# Microcontroller.net
KiCad netlist of a schematic drawn in Altium Designer
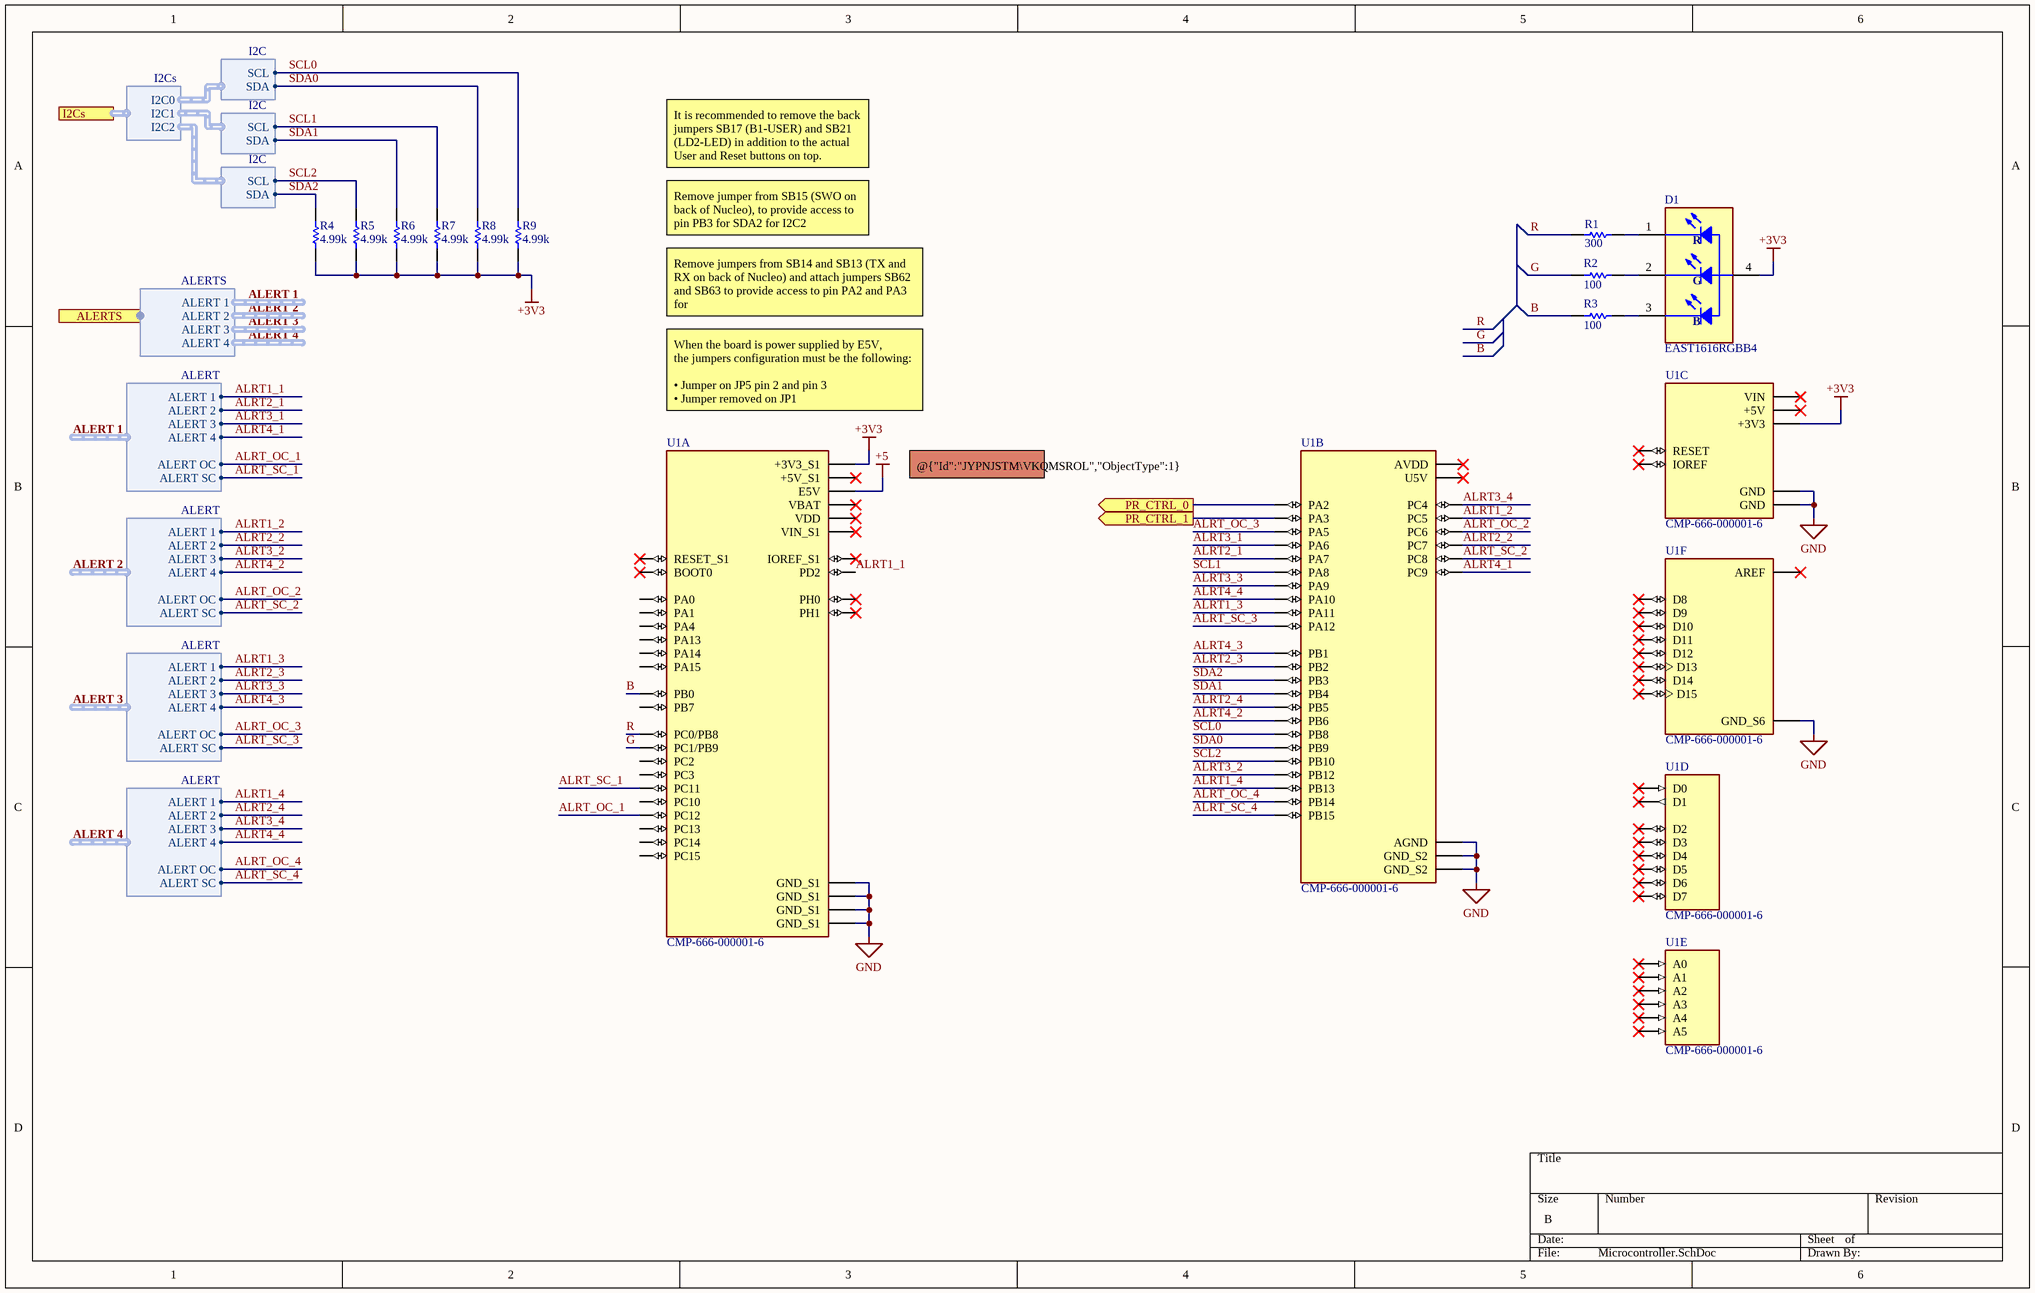
[diagram p0: Microcontroller.SchDoc]

(export (version "E")
  (design (tool "Eeschema 10.0.6"))
  (components
    (comp (ref "D1")
      (value "EAST1616RGBB4")
      (footprint "FP-EAST1616RGBB4-MFG")
      (description "Triple Color LED")
      (libsource (lib "IIT Motorsports") (part "36fc5605c777916eb4f03788a33f3b3"))
    )
    (comp (ref "R1")
      (value "300")
      (footprint "RES 0805_2012")
      (fields
        (field (name "TOLERANCE") "1%")
        (field (name "POWER") "125mW")
        (field (name "Comment") "ERJ-6ENF3000V")
      )
      (libsource (lib "IIT Motorsports") (part "RES"))
    )
    (comp (ref "R2")
      (value "100")
      (footprint "RES 0805_2012")
      (fields
        (field (name "TOLERANCE") "1%")
        (field (name "MP") "CRG0805F100R")
        (field (name "MF") "{'manufacturer': u'TE Connectivity'}")
      )
      (libsource (lib "IIT Motorsports") (part "CMP-009-00299-2"))
    )
    (comp (ref "R3")
      (value "100")
      (footprint "RES 0805_2012")
      (fields
        (field (name "TOLERANCE") "1%")
        (field (name "MP") "CRG0805F100R")
        (field (name "MF") "{'manufacturer': u'TE Connectivity'}")
      )
      (libsource (lib "IIT Motorsports") (part "CMP-009-00299-2"))
    )
    (comp (ref "R4")
      (value "4.99k")
      (footprint "RES 0805_2012")
      (fields
        (field (name "TOLERANCE") "1%")
        (field (name "POWER") "125mW")
        (field (name "Comment") "ERJ-6ENF4991V")
      )
      (libsource (lib "IIT Motorsports") (part "RES"))
    )
    (comp (ref "R5")
      (value "4.99k")
      (footprint "RES 0805_2012")
      (fields
        (field (name "TOLERANCE") "1%")
        (field (name "POWER") "125mW")
        (field (name "Comment") "ERJ-6ENF4991V")
      )
      (libsource (lib "IIT Motorsports") (part "RES"))
    )
    (comp (ref "R6")
      (value "4.99k")
      (footprint "RES 0805_2012")
      (fields
        (field (name "POWER") "125mW")
        (field (name "TOLERANCE") "1%")
        (field (name "Comment") "ERJ-6ENF4991V")
      )
      (libsource (lib "IIT Motorsports") (part "RES"))
    )
    (comp (ref "R7")
      (value "4.99k")
      (footprint "RES 0805_2012")
      (fields
        (field (name "POWER") "125mW")
        (field (name "TOLERANCE") "1%")
        (field (name "Comment") "ERJ-6ENF4991V")
      )
      (libsource (lib "IIT Motorsports") (part "RES"))
    )
    (comp (ref "R8")
      (value "4.99k")
      (footprint "RES 0805_2012")
      (fields
        (field (name "POWER") "125mW")
        (field (name "TOLERANCE") "1%")
        (field (name "Comment") "ERJ-6ENF4991V")
      )
      (libsource (lib "IIT Motorsports") (part "RES"))
    )
    (comp (ref "R9")
      (value "4.99k")
      (footprint "RES 0805_2012")
      (fields
        (field (name "POWER") "125mW")
        (field (name "TOLERANCE") "1%")
        (field (name "Comment") "ERJ-6ENF4991V")
      )
      (libsource (lib "IIT Motorsports") (part "RES"))
    )
    (comp (ref "U1")
      (value "CMP-666-000001-6")
      (footprint "ST_NUCLEO-F401RE")
      (description "STM32F401RE Embedded Nucleo STM32F4 MCU 32-Bit ARM Cortex-M3 Evaluation Board")
      (fields (field (name "MP") "NUCLEO-F401RE") (field (name "MF") "STMicroelectronics"))
      (libsource (lib "IIT Motorsports") (part "CMP-666-000001-6"))
    )
  )
  (nets
    (net (code "7") (name "+3V3") (class "Default")
      (node (ref "D1") (pin "4") (pinfunction "COMMON_ANODE_4") (pintype "passive"))
      (node (ref "R4") (pin "1") (pinfunction "1_1") (pintype "passive"))
      (node (ref "R5") (pin "1") (pinfunction "1_1") (pintype "passive"))
      (node (ref "R6") (pin "1") (pinfunction "1_1") (pintype "passive"))
      (node (ref "R7") (pin "1") (pinfunction "1_1") (pintype "passive"))
      (node (ref "R8") (pin "1") (pinfunction "1_1") (pintype "passive"))
      (node (ref "R9") (pin "1") (pinfunction "1_1") (pintype "passive"))
      (node (ref "U1") (pin "CN6_4") (pinfunction "+3V3_CN6_4") (pintype "power_in"))
      (node (ref "U1") (pin "CN7_16") (pinfunction "+3V3_S1_CN7_16") (pintype "power_in"))
    )
    (net (code "8") (name "+5") (class "Default")
      (node (ref "U1") (pin "CN7_6") (pinfunction "E5V_CN7_6") (pintype "power_in"))
    )
    (net (code "10") (name "/ALRT1_1") (class "Default")
      (node (ref "U1") (pin "CN7_4") (pinfunction "PD2_CN7_4") (pintype "bidirectional"))
    )
    (net (code "11") (name "/ALRT1_2") (class "Default")
      (node (ref "U1") (pin "CN10_6") (pinfunction "PC5_CN10_6") (pintype "bidirectional"))
    )
    (net (code "12") (name "/ALRT1_3") (class "Default")
      (node (ref "U1") (pin "CN10_14") (pinfunction "PA11_CN10_14") (pintype "bidirectional"))
    )
    (net (code "13") (name "/ALRT1_4") (class "Default")
      (node (ref "U1") (pin "CN10_30") (pinfunction "PB13_CN10_30") (pintype "bidirectional"))
    )
    (net (code "14") (name "/ALRT2_1") (class "Default")
      (node (ref "U1") (pin "CN10_15") (pinfunction "PA7_CN10_15") (pintype "bidirectional"))
    )
    (net (code "15") (name "/ALRT2_2") (class "Default")
      (node (ref "U1") (pin "CN10_19") (pinfunction "PC7_CN10_19") (pintype "bidirectional"))
    )
    (net (code "16") (name "/ALRT2_3") (class "Default")
      (node (ref "U1") (pin "CN10_22") (pinfunction "PB2_CN10_22") (pintype "bidirectional"))
    )
    (net (code "17") (name "/ALRT2_4") (class "Default")
      (node (ref "U1") (pin "CN10_29") (pinfunction "PB5_CN10_29") (pintype "bidirectional"))
    )
    (net (code "18") (name "/ALRT3_1") (class "Default")
      (node (ref "U1") (pin "CN10_13") (pinfunction "PA6_CN10_13") (pintype "bidirectional"))
    )
    (net (code "19") (name "/ALRT3_2") (class "Default")
      (node (ref "U1") (pin "CN10_16") (pinfunction "PB12_CN10_16") (pintype "bidirectional"))
    )
    (net (code "20") (name "/ALRT3_3") (class "Default")
      (node (ref "U1") (pin "CN10_21") (pinfunction "PA9_CN10_21") (pintype "bidirectional"))
    )
    (net (code "21") (name "/ALRT3_4") (class "Default")
      (node (ref "U1") (pin "CN10_34") (pinfunction "PC4_CN10_34") (pintype "bidirectional"))
    )
    (net (code "22") (name "/ALRT4_1") (class "Default")
      (node (ref "U1") (pin "CN10_1") (pinfunction "PC9_CN10_1") (pintype "bidirectional"))
    )
    (net (code "23") (name "/ALRT4_2") (class "Default")
      (node (ref "U1") (pin "CN10_17") (pinfunction "PB6_CN10_17") (pintype "bidirectional"))
    )
    (net (code "24") (name "/ALRT4_3") (class "Default")
      (node (ref "U1") (pin "CN10_24") (pinfunction "PB1_CN10_24") (pintype "bidirectional"))
    )
    (net (code "25") (name "/ALRT4_4") (class "Default")
      (node (ref "U1") (pin "CN10_33") (pinfunction "PA10_CN10_33") (pintype "bidirectional"))
    )
    (net (code "26") (name "/ALRT_OC_1") (class "Default")
      (node (ref "U1") (pin "CN7_3") (pinfunction "PC12_CN7_3") (pintype "bidirectional"))
    )
    (net (code "27") (name "/ALRT_OC_2") (class "Default")
      (node (ref "U1") (pin "CN10_4") (pinfunction "PC6_CN10_4") (pintype "bidirectional"))
    )
    (net (code "28") (name "/ALRT_OC_3") (class "Default")
      (node (ref "U1") (pin "CN10_11") (pinfunction "PA5_CN10_11") (pintype "bidirectional"))
    )
    (net (code "29") (name "/ALRT_OC_4") (class "Default")
      (node (ref "U1") (pin "CN10_28") (pinfunction "PB14_CN10_28") (pintype "bidirectional"))
    )
    (net (code "30") (name "/ALRT_SC_1") (class "Default")
      (node (ref "U1") (pin "CN7_2") (pinfunction "PC11_CN7_2") (pintype "bidirectional"))
    )
    (net (code "31") (name "/ALRT_SC_2") (class "Default")
      (node (ref "U1") (pin "CN10_2") (pinfunction "PC8_CN10_2") (pintype "bidirectional"))
    )
    (net (code "32") (name "/ALRT_SC_3") (class "Default")
      (node (ref "U1") (pin "CN10_12") (pinfunction "PA12_CN10_12") (pintype "bidirectional"))
    )
    (net (code "33") (name "/ALRT_SC_4") (class "Default")
      (node (ref "U1") (pin "CN10_26") (pinfunction "PB15_CN10_26") (pintype "bidirectional"))
    )
    (net (code "34") (name "/B") (class "Default")
      (node (ref "R3") (pin "1") (pinfunction "1_1") (pintype "passive"))
      (node (ref "U1") (pin "CN7_34") (pinfunction "PB0_CN7_34") (pintype "bidirectional"))
    )
    (net (code "35") (name "/G") (class "Default")
      (node (ref "R2") (pin "1") (pinfunction "1_1") (pintype "passive"))
      (node (ref "U1") (pin "CN7_36") (pinfunction "PC1/PB9_CN7_36") (pintype "bidirectional"))
    )
    (net (code "37") (name "/PR_CTRL_0") (class "Default")
      (node (ref "U1") (pin "CN10_35") (pinfunction "PA2_CN10_35") (pintype "bidirectional"))
    )
    (net (code "38") (name "/PR_CTRL_1") (class "Default")
      (node (ref "U1") (pin "CN10_37") (pinfunction "PA3_CN10_37") (pintype "bidirectional"))
    )
    (net (code "39") (name "/R") (class "Default")
      (node (ref "R1") (pin "1") (pinfunction "1_1") (pintype "passive"))
      (node (ref "U1") (pin "CN7_38") (pinfunction "PC0/PB8_CN7_38") (pintype "bidirectional"))
    )
    (net (code "40") (name "/SCL0") (class "Default")
      (node (ref "R9") (pin "2") (pinfunction "2_2") (pintype "passive"))
      (node (ref "U1") (pin "CN10_3") (pinfunction "PB8_CN10_3") (pintype "bidirectional"))
    )
    (net (code "41") (name "/SCL1") (class "Default")
      (node (ref "R7") (pin "2") (pinfunction "2_2") (pintype "passive"))
      (node (ref "U1") (pin "CN10_23") (pinfunction "PA8_CN10_23") (pintype "bidirectional"))
    )
    (net (code "42") (name "/SCL2") (class "Default")
      (node (ref "R5") (pin "2") (pinfunction "2_2") (pintype "passive"))
      (node (ref "U1") (pin "CN10_25") (pinfunction "PB10_CN10_25") (pintype "bidirectional"))
    )
    (net (code "43") (name "/SDA0") (class "Default")
      (node (ref "R8") (pin "2") (pinfunction "2_2") (pintype "passive"))
      (node (ref "U1") (pin "CN10_5") (pinfunction "PB9_CN10_5") (pintype "bidirectional"))
    )
    (net (code "44") (name "/SDA1") (class "Default")
      (node (ref "R6") (pin "2") (pinfunction "2_2") (pintype "passive"))
      (node (ref "U1") (pin "CN10_27") (pinfunction "PB4_CN10_27") (pintype "bidirectional"))
    )
    (net (code "45") (name "/SDA2") (class "Default")
      (node (ref "R4") (pin "2") (pinfunction "2_2") (pintype "passive"))
      (node (ref "U1") (pin "CN10_31") (pinfunction "PB3_CN10_31") (pintype "bidirectional"))
    )
    (net (code "54") (name "GND") (class "Default")
      (node (ref "U1") (pin "CN10_20") (pinfunction "GND_S2_CN10_20") (pintype "power_in"))
      (node (ref "U1") (pin "CN10_32") (pinfunction "AGND_CN10_32") (pintype "power_in"))
      (node (ref "U1") (pin "CN10_9") (pinfunction "GND_S2_CN10_9") (pintype "power_in"))
      (node (ref "U1") (pin "CN5_7") (pinfunction "GND_S6_CN5_7") (pintype "power_in"))
      (node (ref "U1") (pin "CN6_6") (pinfunction "GND_CN6_6") (pintype "power_in"))
      (node (ref "U1") (pin "CN6_7") (pinfunction "GND_CN6_7") (pintype "power_in"))
      (node (ref "U1") (pin "CN7_19") (pinfunction "GND_S1_CN7_19") (pintype "power_in"))
      (node (ref "U1") (pin "CN7_20") (pinfunction "GND_S1_CN7_20") (pintype "power_in"))
      (node (ref "U1") (pin "CN7_22") (pinfunction "GND_S1_CN7_22") (pintype "power_in"))
      (node (ref "U1") (pin "CN7_8") (pinfunction "GND_S1_CN7_8") (pintype "power_in"))
    )
    (net (code "55") (name "Net-(D1-BLUE_C)") (class "Default")
      (node (ref "D1") (pin "3") (pinfunction "BLUE_C_3") (pintype "passive"))
      (node (ref "R3") (pin "2") (pinfunction "2_2") (pintype "passive"))
    )
    (net (code "56") (name "Net-(D1-GREEN_C)") (class "Default")
      (node (ref "D1") (pin "2") (pinfunction "GREEN_C_2") (pintype "passive"))
      (node (ref "R2") (pin "2") (pinfunction "2_2") (pintype "passive"))
    )
    (net (code "57") (name "Net-(D1-RED_C)") (class "Default")
      (node (ref "D1") (pin "1") (pinfunction "RED_C_1") (pintype "passive"))
      (node (ref "R1") (pin "2") (pinfunction "2_2") (pintype "passive"))
    )
    (net (code "58") (name "unconnected-(U1A-+5V_S1-PadCN7_18)") (class "Default")
      (node (ref "U1") (pin "CN7_18") (pinfunction "+5V_S1_CN7_18") (pintype "power_in+no_connect"))
    )
    (net (code "59") (name "unconnected-(U1A-BOOT0-PadCN7_7)") (class "Default")
      (node (ref "U1") (pin "CN7_7") (pinfunction "BOOT0_CN7_7") (pintype "bidirectional+no_connect"))
    )
    (net (code "60") (name "unconnected-(U1A-IOREF_S1-PadCN7_12)") (class "Default")
      (node (ref "U1") (pin "CN7_12") (pinfunction "IOREF_S1_CN7_12") (pintype "bidirectional+no_connect"))
    )
    (net (code "61") (name "unconnected-(U1A-PA0-PadCN7_28)") (class "Default")
      (node (ref "U1") (pin "CN7_28") (pinfunction "PA0_CN7_28") (pintype "bidirectional"))
    )
    (net (code "62") (name "unconnected-(U1A-PA1-PadCN7_30)") (class "Default")
      (node (ref "U1") (pin "CN7_30") (pinfunction "PA1_CN7_30") (pintype "bidirectional"))
    )
    (net (code "63") (name "unconnected-(U1A-PA4-PadCN7_32)") (class "Default")
      (node (ref "U1") (pin "CN7_32") (pinfunction "PA4_CN7_32") (pintype "bidirectional"))
    )
    (net (code "64") (name "unconnected-(U1A-PA13-PadCN7_13)") (class "Default")
      (node (ref "U1") (pin "CN7_13") (pinfunction "PA13_CN7_13") (pintype "bidirectional"))
    )
    (net (code "65") (name "unconnected-(U1A-PA14-PadCN7_15)") (class "Default")
      (node (ref "U1") (pin "CN7_15") (pinfunction "PA14_CN7_15") (pintype "bidirectional"))
    )
    (net (code "66") (name "unconnected-(U1A-PA15-PadCN7_17)") (class "Default")
      (node (ref "U1") (pin "CN7_17") (pinfunction "PA15_CN7_17") (pintype "bidirectional"))
    )
    (net (code "67") (name "unconnected-(U1A-PB7-PadCN7_21)") (class "Default")
      (node (ref "U1") (pin "CN7_21") (pinfunction "PB7_CN7_21") (pintype "bidirectional"))
    )
    (net (code "68") (name "unconnected-(U1A-PC2-PadCN7_35)") (class "Default")
      (node (ref "U1") (pin "CN7_35") (pinfunction "PC2_CN7_35") (pintype "bidirectional"))
    )
    (net (code "69") (name "unconnected-(U1A-PC3-PadCN7_37)") (class "Default")
      (node (ref "U1") (pin "CN7_37") (pinfunction "PC3_CN7_37") (pintype "bidirectional"))
    )
    (net (code "70") (name "unconnected-(U1A-PC10-PadCN7_1)") (class "Default")
      (node (ref "U1") (pin "CN7_1") (pinfunction "PC10_CN7_1") (pintype "bidirectional"))
    )
    (net (code "71") (name "unconnected-(U1A-PC13-PadCN7_23)") (class "Default")
      (node (ref "U1") (pin "CN7_23") (pinfunction "PC13_CN7_23") (pintype "bidirectional"))
    )
    (net (code "72") (name "unconnected-(U1A-PC14-PadCN7_25)") (class "Default")
      (node (ref "U1") (pin "CN7_25") (pinfunction "PC14_CN7_25") (pintype "bidirectional"))
    )
    (net (code "73") (name "unconnected-(U1A-PC15-PadCN7_27)") (class "Default")
      (node (ref "U1") (pin "CN7_27") (pinfunction "PC15_CN7_27") (pintype "bidirectional"))
    )
    (net (code "74") (name "unconnected-(U1A-PH0-PadCN7_29)") (class "Default")
      (node (ref "U1") (pin "CN7_29") (pinfunction "PH0_CN7_29") (pintype "bidirectional+no_connect"))
    )
    (net (code "75") (name "unconnected-(U1A-PH1-PadCN7_31)") (class "Default")
      (node (ref "U1") (pin "CN7_31") (pinfunction "PH1_CN7_31") (pintype "bidirectional+no_connect"))
    )
    (net (code "76") (name "unconnected-(U1A-RESET_S1-PadCN7_14)") (class "Default")
      (node (ref "U1") (pin "CN7_14") (pinfunction "RESET_S1_CN7_14") (pintype "bidirectional+no_connect"))
    )
    (net (code "77") (name "unconnected-(U1A-VBAT-PadCN7_33)") (class "Default")
      (node (ref "U1") (pin "CN7_33") (pinfunction "VBAT_CN7_33") (pintype "power_in+no_connect"))
    )
    (net (code "78") (name "unconnected-(U1A-VDD-PadCN7_5)") (class "Default")
      (node (ref "U1") (pin "CN7_5") (pinfunction "VDD_CN7_5") (pintype "power_in+no_connect"))
    )
    (net (code "79") (name "unconnected-(U1A-VIN_S1-PadCN7_24)") (class "Default")
      (node (ref "U1") (pin "CN7_24") (pinfunction "VIN_S1_CN7_24") (pintype "power_in+no_connect"))
    )
    (net (code "80") (name "unconnected-(U1B-AVDD-PadCN10_7)") (class "Default")
      (node (ref "U1") (pin "CN10_7") (pinfunction "AVDD_CN10_7") (pintype "power_in+no_connect"))
    )
    (net (code "81") (name "unconnected-(U1B-U5V-PadCN10_8)") (class "Default")
      (node (ref "U1") (pin "CN10_8") (pinfunction "U5V_CN10_8") (pintype "power_in+no_connect"))
    )
    (net (code "82") (name "unconnected-(U1C-+5V-PadCN6_5)") (class "Default")
      (node (ref "U1") (pin "CN6_5") (pinfunction "+5V_CN6_5") (pintype "power_in+no_connect"))
    )
    (net (code "83") (name "unconnected-(U1C-IOREF-PadCN6_2)") (class "Default")
      (node (ref "U1") (pin "CN6_2") (pinfunction "IOREF_CN6_2") (pintype "bidirectional+no_connect"))
    )
    (net (code "84") (name "unconnected-(U1C-RESET-PadCN6_3)") (class "Default")
      (node (ref "U1") (pin "CN6_3") (pinfunction "RESET_CN6_3") (pintype "bidirectional+no_connect"))
    )
    (net (code "85") (name "unconnected-(U1C-VIN-PadCN6_8)") (class "Default")
      (node (ref "U1") (pin "CN6_8") (pinfunction "VIN_CN6_8") (pintype "power_in+no_connect"))
    )
    (net (code "86") (name "unconnected-(U1D-D0-PadCN9_1)") (class "Default")
      (node (ref "U1") (pin "CN9_1") (pinfunction "D0_CN9_1") (pintype "input+no_connect"))
    )
    (net (code "87") (name "unconnected-(U1D-D1-PadCN9_2)") (class "Default")
      (node (ref "U1") (pin "CN9_2") (pinfunction "D1_CN9_2") (pintype "output+no_connect"))
    )
    (net (code "88") (name "unconnected-(U1D-D2-PadCN9_3)") (class "Default")
      (node (ref "U1") (pin "CN9_3") (pinfunction "D2_CN9_3") (pintype "bidirectional+no_connect"))
    )
    (net (code "89") (name "unconnected-(U1D-D3-PadCN9_4)") (class "Default")
      (node (ref "U1") (pin "CN9_4") (pinfunction "D3_CN9_4") (pintype "bidirectional+no_connect"))
    )
    (net (code "90") (name "unconnected-(U1D-D4-PadCN9_5)") (class "Default")
      (node (ref "U1") (pin "CN9_5") (pinfunction "D4_CN9_5") (pintype "bidirectional+no_connect"))
    )
    (net (code "91") (name "unconnected-(U1D-D5-PadCN9_6)") (class "Default")
      (node (ref "U1") (pin "CN9_6") (pinfunction "D5_CN9_6") (pintype "bidirectional+no_connect"))
    )
    (net (code "92") (name "unconnected-(U1D-D6-PadCN9_7)") (class "Default")
      (node (ref "U1") (pin "CN9_7") (pinfunction "D6_CN9_7") (pintype "bidirectional+no_connect"))
    )
    (net (code "93") (name "unconnected-(U1D-D7-PadCN9_8)") (class "Default")
      (node (ref "U1") (pin "CN9_8") (pinfunction "D7_CN9_8") (pintype "bidirectional+no_connect"))
    )
    (net (code "94") (name "unconnected-(U1E-A0-PadCN8_1)") (class "Default")
      (node (ref "U1") (pin "CN8_1") (pinfunction "A0_CN8_1") (pintype "input+no_connect"))
    )
    (net (code "95") (name "unconnected-(U1E-A1-PadCN8_2)") (class "Default")
      (node (ref "U1") (pin "CN8_2") (pinfunction "A1_CN8_2") (pintype "input+no_connect"))
    )
    (net (code "96") (name "unconnected-(U1E-A2-PadCN8_3)") (class "Default")
      (node (ref "U1") (pin "CN8_3") (pinfunction "A2_CN8_3") (pintype "input+no_connect"))
    )
    (net (code "97") (name "unconnected-(U1E-A3-PadCN8_4)") (class "Default")
      (node (ref "U1") (pin "CN8_4") (pinfunction "A3_CN8_4") (pintype "input+no_connect"))
    )
    (net (code "98") (name "unconnected-(U1E-A4-PadCN8_5)") (class "Default")
      (node (ref "U1") (pin "CN8_5") (pinfunction "A4_CN8_5") (pintype "input+no_connect"))
    )
    (net (code "99") (name "unconnected-(U1E-A5-PadCN8_6)") (class "Default")
      (node (ref "U1") (pin "CN8_6") (pinfunction "A5_CN8_6") (pintype "input+no_connect"))
    )
    (net (code "100") (name "unconnected-(U1F-AREF-PadCN5_8)") (class "Default")
      (node (ref "U1") (pin "CN5_8") (pinfunction "AREF_CN5_8") (pintype "power_in+no_connect"))
    )
    (net (code "101") (name "unconnected-(U1F-D8-PadCN5_1)") (class "Default")
      (node (ref "U1") (pin "CN5_1") (pinfunction "D8_CN5_1") (pintype "bidirectional+no_connect"))
    )
    (net (code "102") (name "unconnected-(U1F-D9-PadCN5_2)") (class "Default")
      (node (ref "U1") (pin "CN5_2") (pinfunction "D9_CN5_2") (pintype "bidirectional+no_connect"))
    )
    (net (code "103") (name "unconnected-(U1F-D10-PadCN5_3)") (class "Default")
      (node (ref "U1") (pin "CN5_3") (pinfunction "D10_CN5_3") (pintype "bidirectional+no_connect"))
    )
    (net (code "104") (name "unconnected-(U1F-D11-PadCN5_4)") (class "Default")
      (node (ref "U1") (pin "CN5_4") (pinfunction "D11_CN5_4") (pintype "bidirectional+no_connect"))
    )
    (net (code "105") (name "unconnected-(U1F-D12-PadCN5_5)") (class "Default")
      (node (ref "U1") (pin "CN5_5") (pinfunction "D12_CN5_5") (pintype "bidirectional+no_connect"))
    )
    (net (code "106") (name "unconnected-(U1F-D13-PadCN5_6)") (class "Default")
      (node (ref "U1") (pin "CN5_6") (pinfunction "D13_CN5_6") (pintype "bidirectional+no_connect"))
    )
    (net (code "107") (name "unconnected-(U1F-D14-PadCN5_9)") (class "Default")
      (node (ref "U1") (pin "CN5_9") (pinfunction "D14_CN5_9") (pintype "bidirectional+no_connect"))
    )
    (net (code "108") (name "unconnected-(U1F-D15-PadCN5_10)") (class "Default")
      (node (ref "U1") (pin "CN5_10") (pinfunction "D15_CN5_10") (pintype "bidirectional+no_connect"))
    )
  )
)
